# Main.net
KiCad netlist of a schematic drawn in Altium Designer
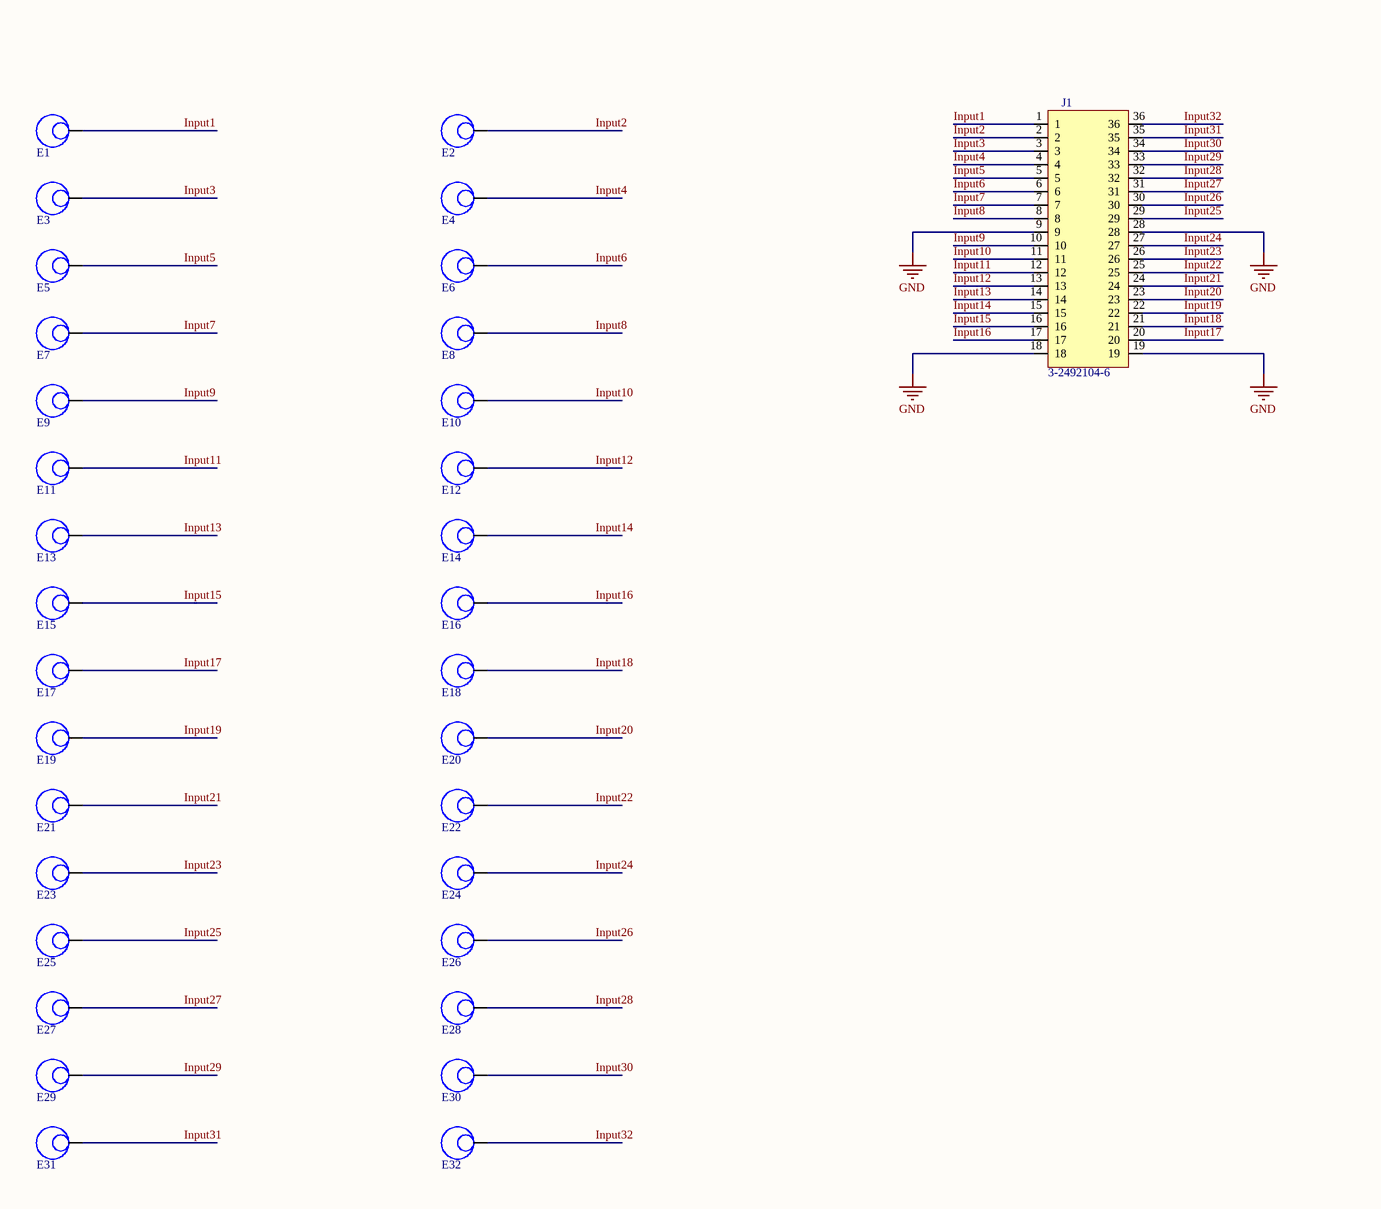
[diagram p0: Main.SchDoc, left]
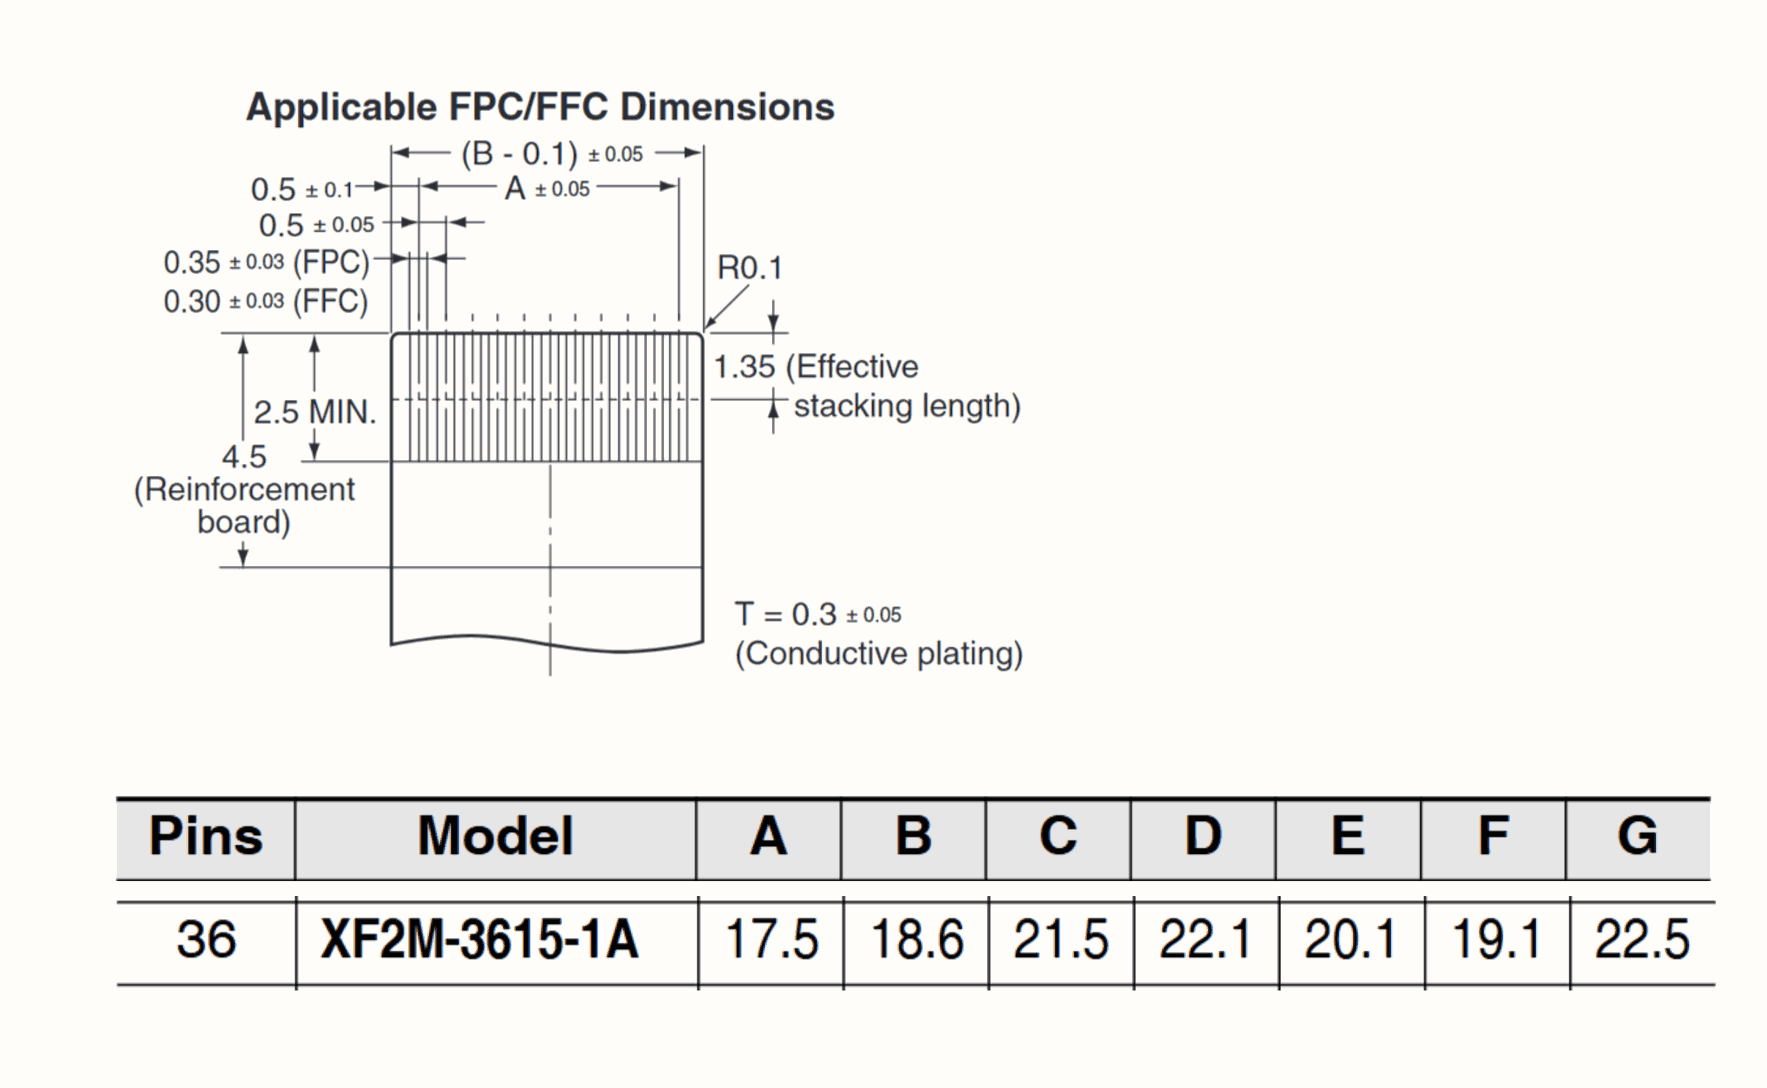
[diagram p1: Main.SchDoc, right]

(export (version "E")
  (design (tool "Eeschema 10.0.6"))
  (components
    (comp (ref "E1")
      (value "UNeedle")
      (footprint "UNeedle")
      (libsource (lib "Microneedle_Lib") (part "UNeedle"))
    )
    (comp (ref "E2")
      (value "UNeedle")
      (footprint "UNeedle")
      (libsource (lib "Microneedle_Lib") (part "UNeedle"))
    )
    (comp (ref "E3")
      (value "UNeedle")
      (footprint "UNeedle")
      (libsource (lib "Microneedle_Lib") (part "UNeedle"))
    )
    (comp (ref "E4")
      (value "UNeedle")
      (footprint "UNeedle")
      (libsource (lib "Microneedle_Lib") (part "UNeedle"))
    )
    (comp (ref "E5")
      (value "UNeedle")
      (footprint "UNeedle")
      (libsource (lib "Microneedle_Lib") (part "UNeedle"))
    )
    (comp (ref "E6")
      (value "UNeedle")
      (footprint "UNeedle")
      (libsource (lib "Microneedle_Lib") (part "UNeedle"))
    )
    (comp (ref "E7")
      (value "UNeedle")
      (footprint "UNeedle")
      (libsource (lib "Microneedle_Lib") (part "UNeedle"))
    )
    (comp (ref "E8")
      (value "UNeedle")
      (footprint "UNeedle")
      (libsource (lib "Microneedle_Lib") (part "UNeedle"))
    )
    (comp (ref "E9")
      (value "UNeedle")
      (footprint "UNeedle")
      (libsource (lib "Microneedle_Lib") (part "UNeedle"))
    )
    (comp (ref "E10")
      (value "UNeedle")
      (footprint "UNeedle")
      (libsource (lib "Microneedle_Lib") (part "UNeedle"))
    )
    (comp (ref "E11")
      (value "UNeedle")
      (footprint "UNeedle")
      (libsource (lib "Microneedle_Lib") (part "UNeedle"))
    )
    (comp (ref "E12")
      (value "UNeedle")
      (footprint "UNeedle")
      (libsource (lib "Microneedle_Lib") (part "UNeedle"))
    )
    (comp (ref "E13")
      (value "UNeedle")
      (footprint "UNeedle")
      (libsource (lib "Microneedle_Lib") (part "UNeedle"))
    )
    (comp (ref "E14")
      (value "UNeedle")
      (footprint "UNeedle")
      (libsource (lib "Microneedle_Lib") (part "UNeedle"))
    )
    (comp (ref "E15")
      (value "UNeedle")
      (footprint "UNeedle")
      (libsource (lib "Microneedle_Lib") (part "UNeedle"))
    )
    (comp (ref "E16")
      (value "UNeedle")
      (footprint "UNeedle")
      (libsource (lib "Microneedle_Lib") (part "UNeedle"))
    )
    (comp (ref "E17")
      (value "UNeedle")
      (footprint "UNeedle")
      (libsource (lib "Microneedle_Lib") (part "UNeedle"))
    )
    (comp (ref "E18")
      (value "UNeedle")
      (footprint "UNeedle")
      (libsource (lib "Microneedle_Lib") (part "UNeedle"))
    )
    (comp (ref "E19")
      (value "UNeedle")
      (footprint "UNeedle")
      (libsource (lib "Microneedle_Lib") (part "UNeedle"))
    )
    (comp (ref "E20")
      (value "UNeedle")
      (footprint "UNeedle")
      (libsource (lib "Microneedle_Lib") (part "UNeedle"))
    )
    (comp (ref "E21")
      (value "UNeedle")
      (footprint "UNeedle")
      (libsource (lib "Microneedle_Lib") (part "UNeedle"))
    )
    (comp (ref "E22")
      (value "UNeedle")
      (footprint "UNeedle")
      (libsource (lib "Microneedle_Lib") (part "UNeedle"))
    )
    (comp (ref "E23")
      (value "UNeedle")
      (footprint "UNeedle")
      (libsource (lib "Microneedle_Lib") (part "UNeedle"))
    )
    (comp (ref "E24")
      (value "UNeedle")
      (footprint "UNeedle")
      (libsource (lib "Microneedle_Lib") (part "UNeedle"))
    )
    (comp (ref "E25")
      (value "UNeedle")
      (footprint "UNeedle")
      (libsource (lib "Microneedle_Lib") (part "UNeedle"))
    )
    (comp (ref "E26")
      (value "UNeedle")
      (footprint "UNeedle")
      (libsource (lib "Microneedle_Lib") (part "UNeedle"))
    )
    (comp (ref "E27")
      (value "UNeedle")
      (footprint "UNeedle")
      (libsource (lib "Microneedle_Lib") (part "UNeedle"))
    )
    (comp (ref "E28")
      (value "UNeedle")
      (footprint "UNeedle")
      (libsource (lib "Microneedle_Lib") (part "UNeedle"))
    )
    (comp (ref "E29")
      (value "UNeedle")
      (footprint "UNeedle")
      (libsource (lib "Microneedle_Lib") (part "UNeedle"))
    )
    (comp (ref "E30")
      (value "UNeedle")
      (footprint "UNeedle")
      (libsource (lib "Microneedle_Lib") (part "UNeedle"))
    )
    (comp (ref "E31")
      (value "UNeedle")
      (footprint "UNeedle")
      (libsource (lib "Microneedle_Lib") (part "UNeedle"))
    )
    (comp (ref "E32")
      (value "UNeedle")
      (footprint "UNeedle")
      (libsource (lib "Microneedle_Lib") (part "UNeedle"))
    )
    (comp (ref "J1")
      (value "3-2492104-6")
      (footprint "Fingers_36POS")
      (libsource (lib "UHDEMG") (part "CON_FINGERS_36POS"))
    )
  )
  (nets
    (net (code "1") (name "/Input1") (class "Default")
      (node (ref "E1") (pin "1") (pinfunction "1_1") (pintype "passive"))
      (node (ref "J1") (pin "1") (pinfunction "1_1") (pintype "passive"))
    )
    (net (code "2") (name "/Input2") (class "Default")
      (node (ref "E2") (pin "1") (pinfunction "1_1") (pintype "passive"))
      (node (ref "J1") (pin "2") (pinfunction "2_2") (pintype "passive"))
    )
    (net (code "3") (name "/Input3") (class "Default")
      (node (ref "E3") (pin "1") (pinfunction "1_1") (pintype "passive"))
      (node (ref "J1") (pin "3") (pinfunction "3_3") (pintype "passive"))
    )
    (net (code "4") (name "/Input4") (class "Default")
      (node (ref "E4") (pin "1") (pinfunction "1_1") (pintype "passive"))
      (node (ref "J1") (pin "4") (pinfunction "4_4") (pintype "passive"))
    )
    (net (code "5") (name "/Input5") (class "Default")
      (node (ref "E5") (pin "1") (pinfunction "1_1") (pintype "passive"))
      (node (ref "J1") (pin "5") (pinfunction "5_5") (pintype "passive"))
    )
    (net (code "6") (name "/Input6") (class "Default")
      (node (ref "E6") (pin "1") (pinfunction "1_1") (pintype "passive"))
      (node (ref "J1") (pin "6") (pinfunction "6_6") (pintype "passive"))
    )
    (net (code "7") (name "/Input7") (class "Default")
      (node (ref "E7") (pin "1") (pinfunction "1_1") (pintype "passive"))
      (node (ref "J1") (pin "7") (pinfunction "7_7") (pintype "passive"))
    )
    (net (code "8") (name "/Input8") (class "Default")
      (node (ref "E8") (pin "1") (pinfunction "1_1") (pintype "passive"))
      (node (ref "J1") (pin "8") (pinfunction "8_8") (pintype "passive"))
    )
    (net (code "9") (name "/Input9") (class "Default")
      (node (ref "E9") (pin "1") (pinfunction "1_1") (pintype "passive"))
      (node (ref "J1") (pin "10") (pinfunction "10_10") (pintype "passive"))
    )
    (net (code "10") (name "/Input10") (class "Default")
      (node (ref "E10") (pin "1") (pinfunction "1_1") (pintype "passive"))
      (node (ref "J1") (pin "11") (pinfunction "11_11") (pintype "passive"))
    )
    (net (code "11") (name "/Input11") (class "Default")
      (node (ref "E11") (pin "1") (pinfunction "1_1") (pintype "passive"))
      (node (ref "J1") (pin "12") (pinfunction "12_12") (pintype "passive"))
    )
    (net (code "12") (name "/Input12") (class "Default")
      (node (ref "E12") (pin "1") (pinfunction "1_1") (pintype "passive"))
      (node (ref "J1") (pin "13") (pinfunction "13_13") (pintype "passive"))
    )
    (net (code "13") (name "/Input13") (class "Default")
      (node (ref "E13") (pin "1") (pinfunction "1_1") (pintype "passive"))
      (node (ref "J1") (pin "14") (pinfunction "14_14") (pintype "passive"))
    )
    (net (code "14") (name "/Input14") (class "Default")
      (node (ref "E14") (pin "1") (pinfunction "1_1") (pintype "passive"))
      (node (ref "J1") (pin "15") (pinfunction "15_15") (pintype "passive"))
    )
    (net (code "15") (name "/Input15") (class "Default")
      (node (ref "E15") (pin "1") (pinfunction "1_1") (pintype "passive"))
      (node (ref "J1") (pin "16") (pinfunction "16_16") (pintype "passive"))
    )
    (net (code "16") (name "/Input16") (class "Default")
      (node (ref "E16") (pin "1") (pinfunction "1_1") (pintype "passive"))
      (node (ref "J1") (pin "17") (pinfunction "17_17") (pintype "passive"))
    )
    (net (code "17") (name "/Input17") (class "Default")
      (node (ref "E17") (pin "1") (pinfunction "1_1") (pintype "passive"))
      (node (ref "J1") (pin "20") (pinfunction "20_20") (pintype "passive"))
    )
    (net (code "18") (name "/Input18") (class "Default")
      (node (ref "E18") (pin "1") (pinfunction "1_1") (pintype "passive"))
      (node (ref "J1") (pin "21") (pinfunction "21_21") (pintype "passive"))
    )
    (net (code "19") (name "/Input19") (class "Default")
      (node (ref "E19") (pin "1") (pinfunction "1_1") (pintype "passive"))
      (node (ref "J1") (pin "22") (pinfunction "22_22") (pintype "passive"))
    )
    (net (code "20") (name "/Input20") (class "Default")
      (node (ref "E20") (pin "1") (pinfunction "1_1") (pintype "passive"))
      (node (ref "J1") (pin "23") (pinfunction "23_23") (pintype "passive"))
    )
    (net (code "21") (name "/Input21") (class "Default")
      (node (ref "E21") (pin "1") (pinfunction "1_1") (pintype "passive"))
      (node (ref "J1") (pin "24") (pinfunction "24_24") (pintype "passive"))
    )
    (net (code "22") (name "/Input22") (class "Default")
      (node (ref "E22") (pin "1") (pinfunction "1_1") (pintype "passive"))
      (node (ref "J1") (pin "25") (pinfunction "25_25") (pintype "passive"))
    )
    (net (code "23") (name "/Input23") (class "Default")
      (node (ref "E23") (pin "1") (pinfunction "1_1") (pintype "passive"))
      (node (ref "J1") (pin "26") (pinfunction "26_26") (pintype "passive"))
    )
    (net (code "24") (name "/Input24") (class "Default")
      (node (ref "E24") (pin "1") (pinfunction "1_1") (pintype "passive"))
      (node (ref "J1") (pin "27") (pinfunction "27_27") (pintype "passive"))
    )
    (net (code "25") (name "/Input25") (class "Default")
      (node (ref "E25") (pin "1") (pinfunction "1_1") (pintype "passive"))
      (node (ref "J1") (pin "29") (pinfunction "29_29") (pintype "passive"))
    )
    (net (code "26") (name "/Input26") (class "Default")
      (node (ref "E26") (pin "1") (pinfunction "1_1") (pintype "passive"))
      (node (ref "J1") (pin "30") (pinfunction "30_30") (pintype "passive"))
    )
    (net (code "27") (name "/Input27") (class "Default")
      (node (ref "E27") (pin "1") (pinfunction "1_1") (pintype "passive"))
      (node (ref "J1") (pin "31") (pinfunction "31_31") (pintype "passive"))
    )
    (net (code "28") (name "/Input28") (class "Default")
      (node (ref "E28") (pin "1") (pinfunction "1_1") (pintype "passive"))
      (node (ref "J1") (pin "32") (pinfunction "32_32") (pintype "passive"))
    )
    (net (code "29") (name "/Input29") (class "Default")
      (node (ref "E29") (pin "1") (pinfunction "1_1") (pintype "passive"))
      (node (ref "J1") (pin "33") (pinfunction "33_33") (pintype "passive"))
    )
    (net (code "30") (name "/Input30") (class "Default")
      (node (ref "E30") (pin "1") (pinfunction "1_1") (pintype "passive"))
      (node (ref "J1") (pin "34") (pinfunction "34_34") (pintype "passive"))
    )
    (net (code "31") (name "/Input31") (class "Default")
      (node (ref "E31") (pin "1") (pinfunction "1_1") (pintype "passive"))
      (node (ref "J1") (pin "35") (pinfunction "35_35") (pintype "passive"))
    )
    (net (code "32") (name "/Input32") (class "Default")
      (node (ref "E32") (pin "1") (pinfunction "1_1") (pintype "passive"))
      (node (ref "J1") (pin "36") (pinfunction "36_36") (pintype "passive"))
    )
    (net (code "33") (name "GND") (class "Default")
      (node (ref "J1") (pin "18") (pinfunction "18_18") (pintype "passive"))
      (node (ref "J1") (pin "19") (pinfunction "19_19") (pintype "passive"))
      (node (ref "J1") (pin "28") (pinfunction "28_28") (pintype "passive"))
      (node (ref "J1") (pin "9") (pinfunction "9_9") (pintype "passive"))
    )
  )
)
